# WL-FRONT.net
KiCad netlist of a schematic drawn in Altium Designer
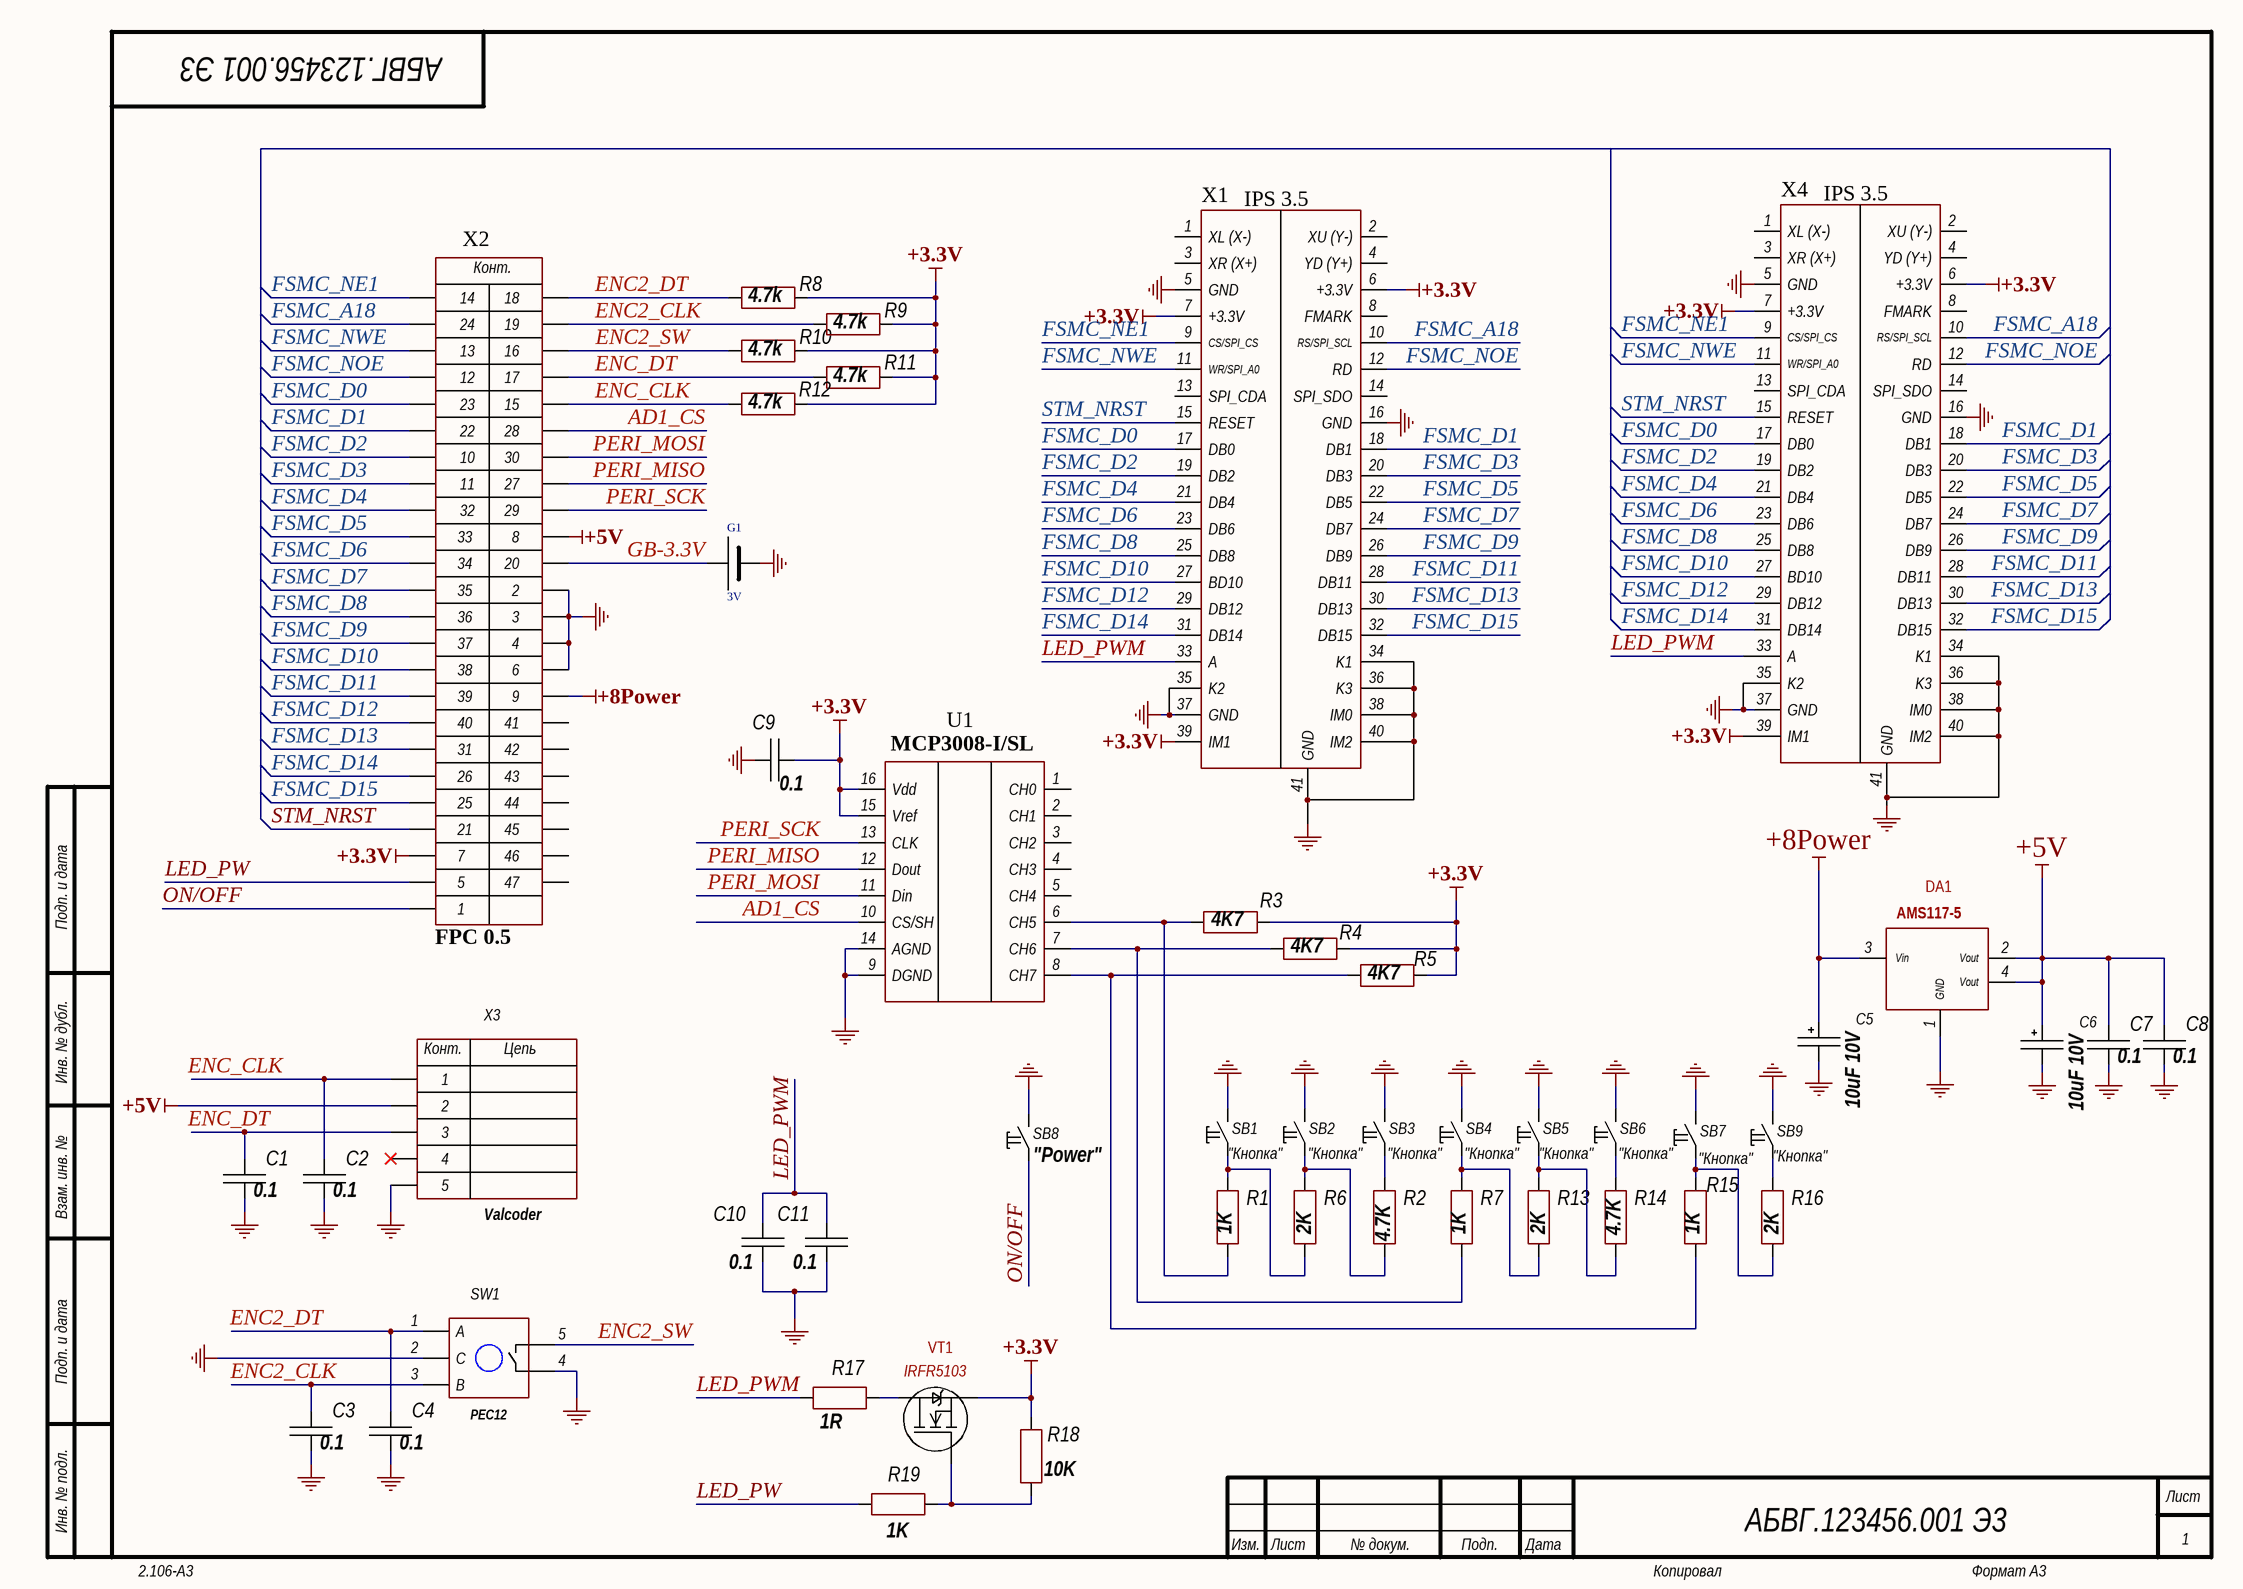
[diagram p0: WL-FRONT.SchDoc]

(export (version "E")
  (design (tool "Eeschema 10.0.6"))
  (components
    (comp (ref "C1")
      (value "0.1")
      (footprint "standard:CH0805C")
      (libsource (lib "Discrete") (part "Capacitor"))
    )
    (comp (ref "C2")
      (value "0.1")
      (footprint "standard:CH0805C")
      (libsource (lib "Discrete") (part "Capacitor"))
    )
    (comp (ref "C3")
      (value "0.1")
      (footprint "standard:CH0805C")
      (libsource (lib "Discrete") (part "Capacitor"))
    )
    (comp (ref "C4")
      (value "0.1")
      (footprint "standard:CH0805C")
      (libsource (lib "Discrete") (part "Capacitor"))
    )
    (comp (ref "C5")
      (value "10uF 10V")
      (footprint "standard:TANTAL_B")
      (libsource (lib "Discrete") (part "TantalCap"))
    )
    (comp (ref "C6")
      (value "10uF 10V")
      (footprint "standard:TANTAL_B")
      (libsource (lib "Discrete") (part "TantalCap"))
    )
    (comp (ref "C7")
      (value "0.1")
      (footprint "standard:CH0805C")
      (libsource (lib "Discrete") (part "Capacitor"))
    )
    (comp (ref "C8")
      (value "0.1")
      (footprint "standard:CH0805C")
      (libsource (lib "Discrete") (part "Capacitor"))
    )
    (comp (ref "C9")
      (value "0.1")
      (footprint "standard:CH0805C")
      (libsource (lib "Discrete") (part "Capacitor"))
    )
    (comp (ref "C10")
      (value "0.1")
      (footprint "standard:CH0805C")
      (libsource (lib "Discrete") (part "Capacitor"))
    )
    (comp (ref "C11")
      (value "0.1")
      (footprint "standard:CH0805C")
      (libsource (lib "Discrete") (part "Capacitor"))
    )
    (comp (ref "DA1") (value "AMS117-5") (footprint "SOT223") (libsource (lib "Analog") (part "AMS117")))
    (comp (ref "G1")
      (value "3V")
      (footprint "BAT: CH224-2032")
      (libsource (lib "Connectors") (part "POWER_BAT"))
    )
    (comp (ref "R1") (value "1K") (footprint "standard:CH0805R") (libsource (lib "") (part "Resistor_3")))
    (comp (ref "R2") (value "4.7K") (footprint "standard:CH0805R") (libsource (lib "") (part "Resistor_3")))
    (comp (ref "R3") (value "4K7") (footprint "standard:CH0805R") (libsource (lib "") (part "Resistor_2")))
    (comp (ref "R4") (value "4K7") (footprint "standard:CH0805R") (libsource (lib "") (part "Resistor_1")))
    (comp (ref "R5") (value "4K7") (footprint "standard:CH0805R") (libsource (lib "") (part "Resistor_2")))
    (comp (ref "R6") (value "2K") (footprint "standard:CH0805R") (libsource (lib "") (part "Resistor_3")))
    (comp (ref "R7") (value "1K") (footprint "standard:CH0805R") (libsource (lib "") (part "Resistor_3")))
    (comp (ref "R8")
      (value "4.7k")
      (footprint "standard:CH0805R")
      (libsource (lib "Discrete") (part "Resistor"))
    )
    (comp (ref "R9")
      (value "4.7k")
      (footprint "standard:CH0805R")
      (libsource (lib "Discrete") (part "Resistor"))
    )
    (comp (ref "R10")
      (value "4.7k")
      (footprint "standard:CH0805R")
      (libsource (lib "Discrete") (part "Resistor"))
    )
    (comp (ref "R11")
      (value "4.7k")
      (footprint "standard:CH0805R")
      (libsource (lib "Discrete") (part "Resistor"))
    )
    (comp (ref "R12")
      (value "4.7k")
      (footprint "standard:CH0805R")
      (libsource (lib "Discrete") (part "Resistor"))
    )
    (comp (ref "R13") (value "2K") (footprint "standard:CH0805R") (libsource (lib "") (part "Resistor_3")))
    (comp (ref "R14") (value "4.7K") (footprint "standard:CH0805R") (libsource (lib "") (part "Resistor_3")))
    (comp (ref "R15") (value "1K") (footprint "standard:CH0805R") (libsource (lib "") (part "Resistor_3")))
    (comp (ref "R16") (value "2K") (footprint "standard:CH0805R") (libsource (lib "") (part "Resistor_3")))
    (comp (ref "R17")
      (value "1R")
      (footprint "standard:CH0805R")
      (libsource (lib "Discrete") (part "Resistor"))
    )
    (comp (ref "R18") (value "10K") (footprint "standard:CH0805R") (libsource (lib "") (part "Resistor_3")))
    (comp (ref "R19")
      (value "1K")
      (footprint "standard:CH0805R")
      (libsource (lib "Discrete") (part "Resistor"))
    )
    (comp (ref "SB1")
      (value "\"Кнопка\"")
      (footprint "BUT: 5X5")
      (description "6x6 mm")
      (libsource (lib "Connectors") (part "Tactile switches"))
    )
    (comp (ref "SB2")
      (value "\"Кнопка\"")
      (footprint "BUT: 5X5")
      (description "6x6 mm")
      (libsource (lib "Connectors") (part "Tactile switches"))
    )
    (comp (ref "SB3")
      (value "\"Кнопка\"")
      (footprint "BUT: 5X5")
      (description "6x6 mm")
      (libsource (lib "Connectors") (part "Tactile switches"))
    )
    (comp (ref "SB4")
      (value "\"Кнопка\"")
      (footprint "BUT: 5X5")
      (description "6x6 mm")
      (libsource (lib "Connectors") (part "Tactile switches"))
    )
    (comp (ref "SB5")
      (value "\"Кнопка\"")
      (footprint "BUT: 5X5")
      (description "6x6 mm")
      (libsource (lib "Connectors") (part "Tactile switches"))
    )
    (comp (ref "SB6")
      (value "\"Кнопка\"")
      (footprint "BUT: 5X5")
      (description "6x6 mm")
      (libsource (lib "Connectors") (part "Tactile switches"))
    )
    (comp (ref "SB7")
      (value "\"Кнопка\"")
      (footprint "BUT: 5X5")
      (description "6x6 mm")
      (libsource (lib "Connectors") (part "Tactile switches"))
    )
    (comp (ref "SB8")
      (value "\"Power\"")
      (footprint "BUT: 5X5")
      (description "6x6 mm")
      (libsource (lib "Connectors") (part "Tactile switches"))
    )
    (comp (ref "SB9")
      (value "\"Кнопка\"")
      (footprint "BUT: 5X5")
      (description "6x6 mm")
      (libsource (lib "Connectors") (part "Tactile switches"))
    )
    (comp (ref "SW1")
      (value "PEC12")
      (footprint "Valkoder-m2")
      (description "Encoder")
      (libsource (lib "Connectors") (part "PEC12"))
    )
    (comp (ref "U1")
      (value "MCP3008-I/SL")
      (footprint "16-SOIC")
      (libsource (lib "Digital") (part "MCP3008-I/SL"))
    )
    (comp (ref "VT1")
      (value "IRFR5103")
      (footprint "SOT23_132")
      (libsource (lib "Transistor") (part "N-KANAL"))
    )
    (comp (ref "X1")
      (value "IPS 3.5")
      (footprint "FPC-40P 0.5mm")
      (libsource (lib "") (part "LCD-IPS 3.5_1"))
    )
    (comp (ref "X2")
      (value "FPC 0.5")
      (footprint "CON: PBD2x20")
      (libsource (lib "Connectors") (part "FPC-45-0.5"))
    )
    (comp (ref "X3")
      (value "Valcoder")
      (footprint "custom:CON: PLS-5")
      (libsource (lib "Connectors") (part "5-Connector"))
    )
    (comp (ref "X4")
      (value "IPS 3.5")
      (footprint "IPS 3.5 ILI9481")
      (libsource (lib "Digital") (part "LCD-IPS 3.5"))
    )
  )
  (nets
    (net (code "1") (name "+3.3V") (class "Default")
      (node (ref "C9") (pin "2") (pinfunction "2_2") (pintype "power_in"))
      (node (ref "R10") (pin "1") (pinfunction "1_1") (pintype "passive"))
      (node (ref "R11") (pin "1") (pinfunction "1_1") (pintype "passive"))
      (node (ref "R12") (pin "1") (pinfunction "1_1") (pintype "passive"))
      (node (ref "R18") (pin "2") (pinfunction "2_2") (pintype "passive"))
      (node (ref "R3") (pin "2") (pinfunction "2_2") (pintype "passive"))
      (node (ref "R4") (pin "2") (pinfunction "2_2") (pintype "passive"))
      (node (ref "R5") (pin "2") (pinfunction "2_2") (pintype "passive"))
      (node (ref "R8") (pin "1") (pinfunction "1_1") (pintype "passive"))
      (node (ref "R9") (pin "1") (pinfunction "1_1") (pintype "passive"))
      (node (ref "U1") (pin "15") (pinfunction "Vref_15") (pintype "passive"))
      (node (ref "U1") (pin "16") (pinfunction "Vdd_16") (pintype "passive"))
      (node (ref "VT1") (pin "2") (pinfunction "I_2") (pintype "passive"))
      (node (ref "X1") (pin "39") (pinfunction "IM1_39") (pintype "passive"))
      (node (ref "X1") (pin "6") (pinfunction "+3.3V_6") (pintype "passive"))
      (node (ref "X1") (pin "7") (pinfunction "+3.3V_7") (pintype "passive"))
      (node (ref "X2") (pin "7") (pinfunction "7_7") (pintype "power_in"))
      (node (ref "X4") (pin "39") (pinfunction "IM1_39") (pintype "passive"))
      (node (ref "X4") (pin "6") (pinfunction "+3.3V_6") (pintype "passive"))
      (node (ref "X4") (pin "7") (pinfunction "+3.3V_7") (pintype "passive"))
    )
    (net (code "2") (name "+5V") (class "Default")
      (node (ref "C6") (pin "1") (pinfunction "1_1") (pintype "power_in"))
      (node (ref "C7") (pin "1") (pinfunction "1_1") (pintype "power_in"))
      (node (ref "C8") (pin "1") (pinfunction "1_1") (pintype "power_in"))
      (node (ref "DA1") (pin "2") (pinfunction "Vout_2") (pintype "passive"))
      (node (ref "DA1") (pin "4") (pinfunction "Vout_4") (pintype "passive"))
      (node (ref "X2") (pin "8") (pinfunction "8_8") (pintype "power_in"))
      (node (ref "X3") (pin "2") (pinfunction "2_2") (pintype "passive"))
    )
    (net (code "3") (name "+8Power") (class "Default")
      (node (ref "C5") (pin "1") (pinfunction "1_1") (pintype "power_in"))
      (node (ref "DA1") (pin "3") (pinfunction "Vin_3") (pintype "passive"))
      (node (ref "X2") (pin "9") (pinfunction "9_9") (pintype "power_in"))
    )
    (net (code "4") (name "/AD1_CS") (class "Default")
      (node (ref "U1") (pin "10") (pinfunction "CS/SH_10") (pintype "passive"))
      (node (ref "X2") (pin "28") (pinfunction "28_28") (pintype "power_in"))
    )
    (net (code "5") (name "/ENC2_CLK") (class "Default")
      (node (ref "C3") (pin "1") (pinfunction "1_1") (pintype "power_in"))
      (node (ref "R9") (pin "2") (pinfunction "2_2") (pintype "passive"))
      (node (ref "SW1") (pin "3") (pinfunction "B_3") (pintype "passive"))
      (node (ref "X2") (pin "19") (pinfunction "19_19") (pintype "power_in"))
    )
    (net (code "6") (name "/ENC2_DT") (class "Default")
      (node (ref "C4") (pin "1") (pinfunction "1_1") (pintype "power_in"))
      (node (ref "R8") (pin "2") (pinfunction "2_2") (pintype "passive"))
      (node (ref "SW1") (pin "1") (pinfunction "A_1") (pintype "passive"))
      (node (ref "X2") (pin "18") (pinfunction "18_18") (pintype "power_in"))
    )
    (net (code "7") (name "/ENC2_SW") (class "Default")
      (node (ref "R10") (pin "2") (pinfunction "2_2") (pintype "passive"))
      (node (ref "SW1") (pin "5") (pinfunction "5_5") (pintype "passive"))
      (node (ref "X2") (pin "16") (pinfunction "16_16") (pintype "power_in"))
    )
    (net (code "8") (name "/ENC_CLK") (class "Default")
      (node (ref "C2") (pin "1") (pinfunction "1_1") (pintype "power_in"))
      (node (ref "R12") (pin "2") (pinfunction "2_2") (pintype "passive"))
      (node (ref "X2") (pin "15") (pinfunction "15_15") (pintype "power_in"))
      (node (ref "X3") (pin "1") (pinfunction "1_1") (pintype "passive"))
    )
    (net (code "9") (name "/ENC_DT") (class "Default")
      (node (ref "C1") (pin "1") (pinfunction "1_1") (pintype "power_in"))
      (node (ref "R11") (pin "2") (pinfunction "2_2") (pintype "passive"))
      (node (ref "X2") (pin "17") (pinfunction "17_17") (pintype "power_in"))
      (node (ref "X3") (pin "3") (pinfunction "3_3") (pintype "power_in"))
    )
    (net (code "10") (name "/FSMC_A18") (class "Default")
      (node (ref "X1") (pin "10") (pinfunction "RS/SPI_SCL_10") (pintype "passive"))
      (node (ref "X2") (pin "24") (pinfunction "24_24") (pintype "passive"))
      (node (ref "X4") (pin "10") (pinfunction "RS/SPI_SCL_10") (pintype "passive"))
    )
    (net (code "11") (name "/FSMC_D0") (class "Default")
      (node (ref "X1") (pin "17") (pinfunction "DB0_17") (pintype "passive"))
      (node (ref "X2") (pin "23") (pinfunction "23_23") (pintype "power_in"))
      (node (ref "X4") (pin "17") (pinfunction "DB0_17") (pintype "passive"))
    )
    (net (code "12") (name "/FSMC_D1") (class "Default")
      (node (ref "X1") (pin "18") (pinfunction "DB1_18") (pintype "passive"))
      (node (ref "X2") (pin "22") (pinfunction "22_22") (pintype "power_in"))
      (node (ref "X4") (pin "18") (pinfunction "DB1_18") (pintype "passive"))
    )
    (net (code "13") (name "/FSMC_D2") (class "Default")
      (node (ref "X1") (pin "19") (pinfunction "DB2_19") (pintype "passive"))
      (node (ref "X2") (pin "10") (pinfunction "10_10") (pintype "power_in"))
      (node (ref "X4") (pin "19") (pinfunction "DB2_19") (pintype "passive"))
    )
    (net (code "14") (name "/FSMC_D3") (class "Default")
      (node (ref "X1") (pin "20") (pinfunction "DB3_20") (pintype "passive"))
      (node (ref "X2") (pin "11") (pinfunction "11_11") (pintype "power_in"))
      (node (ref "X4") (pin "20") (pinfunction "DB3_20") (pintype "passive"))
    )
    (net (code "15") (name "/FSMC_D4") (class "Default")
      (node (ref "X1") (pin "21") (pinfunction "DB4_21") (pintype "passive"))
      (node (ref "X2") (pin "32") (pinfunction "32_32") (pintype "power_in"))
      (node (ref "X4") (pin "21") (pinfunction "DB4_21") (pintype "passive"))
    )
    (net (code "16") (name "/FSMC_D5") (class "Default")
      (node (ref "X1") (pin "22") (pinfunction "DB5_22") (pintype "passive"))
      (node (ref "X2") (pin "33") (pinfunction "33_33") (pintype "power_in"))
      (node (ref "X4") (pin "22") (pinfunction "DB5_22") (pintype "passive"))
    )
    (net (code "17") (name "/FSMC_D6") (class "Default")
      (node (ref "X1") (pin "23") (pinfunction "DB6_23") (pintype "passive"))
      (node (ref "X2") (pin "34") (pinfunction "34_34") (pintype "power_in"))
      (node (ref "X4") (pin "23") (pinfunction "DB6_23") (pintype "passive"))
    )
    (net (code "18") (name "/FSMC_D7") (class "Default")
      (node (ref "X1") (pin "24") (pinfunction "DB7_24") (pintype "passive"))
      (node (ref "X2") (pin "35") (pinfunction "35_35") (pintype "power_in"))
      (node (ref "X4") (pin "24") (pinfunction "DB7_24") (pintype "passive"))
    )
    (net (code "19") (name "/FSMC_D8") (class "Default")
      (node (ref "X1") (pin "25") (pinfunction "DB8_25") (pintype "passive"))
      (node (ref "X2") (pin "36") (pinfunction "36_36") (pintype "power_in"))
      (node (ref "X4") (pin "25") (pinfunction "DB8_25") (pintype "passive"))
    )
    (net (code "20") (name "/FSMC_D9") (class "Default")
      (node (ref "X1") (pin "26") (pinfunction "DB9_26") (pintype "passive"))
      (node (ref "X2") (pin "37") (pinfunction "37_37") (pintype "power_in"))
      (node (ref "X4") (pin "26") (pinfunction "DB9_26") (pintype "passive"))
    )
    (net (code "21") (name "/FSMC_D10") (class "Default")
      (node (ref "X1") (pin "27") (pinfunction "BD10_27") (pintype "passive"))
      (node (ref "X2") (pin "38") (pinfunction "38_38") (pintype "power_in"))
      (node (ref "X4") (pin "27") (pinfunction "BD10_27") (pintype "passive"))
    )
    (net (code "22") (name "/FSMC_D11") (class "Default")
      (node (ref "X1") (pin "28") (pinfunction "DB11_28") (pintype "passive"))
      (node (ref "X2") (pin "39") (pinfunction "39_39") (pintype "power_in"))
      (node (ref "X4") (pin "28") (pinfunction "DB11_28") (pintype "passive"))
    )
    (net (code "23") (name "/FSMC_D12") (class "Default")
      (node (ref "X1") (pin "29") (pinfunction "DB12_29") (pintype "passive"))
      (node (ref "X2") (pin "40") (pinfunction "40_40") (pintype "power_in"))
      (node (ref "X4") (pin "29") (pinfunction "DB12_29") (pintype "passive"))
    )
    (net (code "24") (name "/FSMC_D13") (class "Default")
      (node (ref "X1") (pin "30") (pinfunction "DB13_30") (pintype "passive"))
      (node (ref "X2") (pin "31") (pinfunction "31_31") (pintype "power_in"))
      (node (ref "X4") (pin "30") (pinfunction "DB13_30") (pintype "passive"))
    )
    (net (code "25") (name "/FSMC_D14") (class "Default")
      (node (ref "X1") (pin "31") (pinfunction "DB14_31") (pintype "passive"))
      (node (ref "X2") (pin "26") (pinfunction "26_26") (pintype "power_in"))
      (node (ref "X4") (pin "31") (pinfunction "DB14_31") (pintype "passive"))
    )
    (net (code "26") (name "/FSMC_D15") (class "Default")
      (node (ref "X1") (pin "32") (pinfunction "DB15_32") (pintype "passive"))
      (node (ref "X2") (pin "25") (pinfunction "25_25") (pintype "power_in"))
      (node (ref "X4") (pin "32") (pinfunction "DB15_32") (pintype "passive"))
    )
    (net (code "27") (name "/FSMC_NE1") (class "Default")
      (node (ref "X1") (pin "9") (pinfunction "CS/SPI_CS_9") (pintype "passive"))
      (node (ref "X2") (pin "14") (pinfunction "14_14") (pintype "passive"))
      (node (ref "X4") (pin "9") (pinfunction "CS/SPI_CS_9") (pintype "passive"))
    )
    (net (code "28") (name "/FSMC_NOE") (class "Default")
      (node (ref "X1") (pin "12") (pinfunction "RD_12") (pintype "passive"))
      (node (ref "X2") (pin "12") (pinfunction "12_12") (pintype "power_in"))
      (node (ref "X4") (pin "12") (pinfunction "RD_12") (pintype "passive"))
    )
    (net (code "29") (name "/FSMC_NWE") (class "Default")
      (node (ref "X1") (pin "11") (pinfunction "WR/SPI_A0_11") (pintype "passive"))
      (node (ref "X2") (pin "13") (pinfunction "13_13") (pintype "power_in"))
      (node (ref "X4") (pin "11") (pinfunction "WR/SPI_A0_11") (pintype "passive"))
    )
    (net (code "30") (name "/GB-3.3V") (class "Default")
      (node (ref "G1") (pin "1") (pinfunction "0_1") (pintype "passive"))
      (node (ref "X2") (pin "20") (pinfunction "20_20") (pintype "power_in"))
    )
    (net (code "31") (name "/LED_PW") (class "Default")
      (node (ref "R19") (pin "2") (pinfunction "2_2") (pintype "passive"))
      (node (ref "X2") (pin "5") (pinfunction "5_5") (pintype "power_in"))
    )
    (net (code "32") (name "/LED_PWM") (class "Default")
      (node (ref "C10") (pin "1") (pinfunction "1_1") (pintype "power_in"))
      (node (ref "C11") (pin "1") (pinfunction "1_1") (pintype "power_in"))
      (node (ref "R17") (pin "2") (pinfunction "2_2") (pintype "passive"))
      (node (ref "X1") (pin "33") (pinfunction "A_33") (pintype "passive"))
      (node (ref "X4") (pin "33") (pinfunction "A_33") (pintype "passive"))
    )
    (net (code "33") (name "/ON{slash}OFF") (class "Default")
      (node (ref "SB8") (pin "1") (pinfunction "1_1") (pintype "passive"))
      (node (ref "X2") (pin "1") (pinfunction "1_1") (pintype "power_in"))
    )
    (net (code "34") (name "/PERI_MISO") (class "Default")
      (node (ref "U1") (pin "12") (pinfunction "Dout_12") (pintype "passive"))
      (node (ref "X2") (pin "27") (pinfunction "27_27") (pintype "power_in"))
    )
    (net (code "35") (name "/PERI_MOSI") (class "Default")
      (node (ref "U1") (pin "11") (pinfunction "Din_11") (pintype "passive"))
      (node (ref "X2") (pin "30") (pinfunction "30_30") (pintype "power_in"))
    )
    (net (code "36") (name "/PERI_SCK") (class "Default")
      (node (ref "U1") (pin "13") (pinfunction "CLK_13") (pintype "passive"))
      (node (ref "X2") (pin "29") (pinfunction "29_29") (pintype "power_in"))
    )
    (net (code "37") (name "/STM_NRST") (class "Default")
      (node (ref "X1") (pin "15") (pinfunction "RESET_15") (pintype "passive"))
      (node (ref "X2") (pin "21") (pinfunction "21_21") (pintype "power_in"))
      (node (ref "X4") (pin "15") (pinfunction "RESET_15") (pintype "passive"))
    )
    (net (code "38") (name "GND") (class "Default")
      (node (ref "C1") (pin "2") (pinfunction "2_2") (pintype "power_in"))
      (node (ref "C10") (pin "2") (pinfunction "2_2") (pintype "power_in"))
      (node (ref "C11") (pin "2") (pinfunction "2_2") (pintype "power_in"))
      (node (ref "C2") (pin "2") (pinfunction "2_2") (pintype "power_in"))
      (node (ref "C3") (pin "2") (pinfunction "2_2") (pintype "power_in"))
      (node (ref "C4") (pin "2") (pinfunction "2_2") (pintype "power_in"))
      (node (ref "C5") (pin "2") (pinfunction "2_2") (pintype "power_in"))
      (node (ref "C6") (pin "2") (pinfunction "2_2") (pintype "power_in"))
      (node (ref "C7") (pin "2") (pinfunction "2_2") (pintype "power_in"))
      (node (ref "C8") (pin "2") (pinfunction "2_2") (pintype "power_in"))
      (node (ref "C9") (pin "1") (pinfunction "1_1") (pintype "power_in"))
      (node (ref "DA1") (pin "1") (pinfunction "GND_1") (pintype "passive"))
      (node (ref "G1") (pin "2") (pinfunction "1_2") (pintype "passive"))
      (node (ref "SB1") (pin "2") (pinfunction "2_2") (pintype "passive"))
      (node (ref "SB2") (pin "2") (pinfunction "2_2") (pintype "passive"))
      (node (ref "SB3") (pin "2") (pinfunction "2_2") (pintype "passive"))
      (node (ref "SB4") (pin "2") (pinfunction "2_2") (pintype "passive"))
      (node (ref "SB5") (pin "2") (pinfunction "2_2") (pintype "passive"))
      (node (ref "SB6") (pin "2") (pinfunction "2_2") (pintype "passive"))
      (node (ref "SB7") (pin "2") (pinfunction "2_2") (pintype "passive"))
      (node (ref "SB8") (pin "2") (pinfunction "2_2") (pintype "passive"))
      (node (ref "SB9") (pin "2") (pinfunction "2_2") (pintype "passive"))
      (node (ref "SW1") (pin "2") (pinfunction "C_2") (pintype "passive"))
      (node (ref "SW1") (pin "4") (pinfunction "4_4") (pintype "passive"))
      (node (ref "U1") (pin "14") (pinfunction "AGND_14") (pintype "passive"))
      (node (ref "U1") (pin "9") (pinfunction "DGND_9") (pintype "passive"))
      (node (ref "X1") (pin "16") (pinfunction "GND_16") (pintype "passive"))
      (node (ref "X1") (pin "34") (pinfunction "K1_34") (pintype "passive"))
      (node (ref "X1") (pin "35") (pinfunction "K2_35") (pintype "passive"))
      (node (ref "X1") (pin "36") (pinfunction "K3_36") (pintype "passive"))
      (node (ref "X1") (pin "37") (pinfunction "GND_37") (pintype "passive"))
      (node (ref "X1") (pin "38") (pinfunction "IM0_38") (pintype "passive"))
      (node (ref "X1") (pin "40") (pinfunction "IM2_40") (pintype "passive"))
      (node (ref "X1") (pin "41") (pinfunction "GND_41") (pintype "passive"))
      (node (ref "X1") (pin "5") (pinfunction "GND_5") (pintype "passive"))
      (node (ref "X2") (pin "2") (pinfunction "2_2") (pintype "power_in"))
      (node (ref "X2") (pin "3") (pinfunction "3_3") (pintype "power_in"))
      (node (ref "X2") (pin "4") (pinfunction "4_4") (pintype "power_in"))
      (node (ref "X2") (pin "6") (pinfunction "6_6") (pintype "power_in"))
      (node (ref "X3") (pin "5") (pinfunction "5_5") (pintype "power_in"))
      (node (ref "X4") (pin "16") (pinfunction "GND_16") (pintype "passive"))
      (node (ref "X4") (pin "34") (pinfunction "K1_34") (pintype "passive"))
      (node (ref "X4") (pin "35") (pinfunction "K2_35") (pintype "passive"))
      (node (ref "X4") (pin "36") (pinfunction "K3_36") (pintype "passive"))
      (node (ref "X4") (pin "37") (pinfunction "GND_37") (pintype "passive"))
      (node (ref "X4") (pin "38") (pinfunction "IM0_38") (pintype "passive"))
      (node (ref "X4") (pin "40") (pinfunction "IM2_40") (pintype "passive"))
      (node (ref "X4") (pin "41") (pinfunction "GND_41") (pintype "passive"))
      (node (ref "X4") (pin "5") (pinfunction "GND_5") (pintype "passive"))
    )
    (net (code "39") (name "Net-(R1-Pad2)") (class "Default")
      (node (ref "R1") (pin "2") (pinfunction "2_2") (pintype "passive"))
      (node (ref "R6") (pin "1") (pinfunction "1_1") (pintype "passive"))
      (node (ref "SB1") (pin "1") (pinfunction "1_1") (pintype "passive"))
    )
    (net (code "40") (name "Net-(R2-Pad1)") (class "Default")
      (node (ref "R2") (pin "1") (pinfunction "1_1") (pintype "passive"))
      (node (ref "R6") (pin "2") (pinfunction "2_2") (pintype "passive"))
      (node (ref "SB2") (pin "1") (pinfunction "1_1") (pintype "passive"))
    )
    (net (code "41") (name "Net-(R2-Pad2)") (class "Default")
      (node (ref "R2") (pin "2") (pinfunction "2_2") (pintype "passive"))
      (node (ref "SB3") (pin "1") (pinfunction "1_1") (pintype "passive"))
    )
    (net (code "42") (name "Net-(R13-Pad1)") (class "Default")
      (node (ref "R13") (pin "1") (pinfunction "1_1") (pintype "passive"))
      (node (ref "R7") (pin "2") (pinfunction "2_2") (pintype "passive"))
      (node (ref "SB4") (pin "1") (pinfunction "1_1") (pintype "passive"))
    )
    (net (code "43") (name "Net-(R13-Pad2)") (class "Default")
      (node (ref "R13") (pin "2") (pinfunction "2_2") (pintype "passive"))
      (node (ref "R14") (pin "1") (pinfunction "1_1") (pintype "passive"))
      (node (ref "SB5") (pin "1") (pinfunction "1_1") (pintype "passive"))
    )
    (net (code "44") (name "Net-(R14-Pad2)") (class "Default")
      (node (ref "R14") (pin "2") (pinfunction "2_2") (pintype "passive"))
      (node (ref "SB6") (pin "1") (pinfunction "1_1") (pintype "passive"))
    )
    (net (code "45") (name "Net-(R15-Pad2)") (class "Default")
      (node (ref "R15") (pin "2") (pinfunction "2_2") (pintype "passive"))
      (node (ref "R16") (pin "1") (pinfunction "1_1") (pintype "passive"))
      (node (ref "SB7") (pin "1") (pinfunction "1_1") (pintype "passive"))
    )
    (net (code "46") (name "Net-(R16-Pad2)") (class "Default")
      (node (ref "R16") (pin "2") (pinfunction "2_2") (pintype "passive"))
      (node (ref "SB9") (pin "1") (pinfunction "1_1") (pintype "passive"))
    )
    (net (code "47") (name "Net-(U1-CH5)") (class "Default")
      (node (ref "R1") (pin "1") (pinfunction "1_1") (pintype "passive"))
      (node (ref "R3") (pin "1") (pinfunction "1_1") (pintype "passive"))
      (node (ref "U1") (pin "6") (pinfunction "CH5_6") (pintype "passive"))
    )
    (net (code "48") (name "Net-(U1-CH6)") (class "Default")
      (node (ref "R4") (pin "1") (pinfunction "1_1") (pintype "passive"))
      (node (ref "R7") (pin "1") (pinfunction "1_1") (pintype "passive"))
      (node (ref "U1") (pin "7") (pinfunction "CH6_7") (pintype "passive"))
    )
    (net (code "49") (name "Net-(U1-CH7)") (class "Default")
      (node (ref "R15") (pin "1") (pinfunction "1_1") (pintype "passive"))
      (node (ref "R5") (pin "1") (pinfunction "1_1") (pintype "passive"))
      (node (ref "U1") (pin "8") (pinfunction "CH7_8") (pintype "passive"))
    )
    (net (code "50") (name "Net-(VT1-Затвор(Gate))") (class "Default")
      (node (ref "R18") (pin "1") (pinfunction "1_1") (pintype "passive"))
      (node (ref "R19") (pin "1") (pinfunction "1_1") (pintype "passive"))
      (node (ref "VT1") (pin "1") (pinfunction "Затвор(Gate)_1") (pintype "passive"))
    )
    (net (code "51") (name "Net-(VT1-Сток(Drain))") (class "Default")
      (node (ref "R17") (pin "1") (pinfunction "1_1") (pintype "passive"))
      (node (ref "VT1") (pin "3") (pinfunction "Сток(Drain)_3") (pintype "passive"))
    )
    (net (code "52") (name "unconnected-(U1-CH0-Pad1)") (class "Default")
      (node (ref "U1") (pin "1") (pinfunction "CH0_1") (pintype "passive"))
    )
    (net (code "53") (name "unconnected-(U1-CH1-Pad2)") (class "Default")
      (node (ref "U1") (pin "2") (pinfunction "CH1_2") (pintype "passive"))
    )
    (net (code "54") (name "unconnected-(U1-CH2-Pad3)") (class "Default")
      (node (ref "U1") (pin "3") (pinfunction "CH2_3") (pintype "passive"))
    )
    (net (code "55") (name "unconnected-(U1-CH3-Pad4)") (class "Default")
      (node (ref "U1") (pin "4") (pinfunction "CH3_4") (pintype "passive"))
    )
    (net (code "56") (name "unconnected-(U1-CH4-Pad5)") (class "Default")
      (node (ref "U1") (pin "5") (pinfunction "CH4_5") (pintype "passive"))
    )
    (net (code "57") (name "unconnected-(X1-FMARK-Pad8)") (class "Default")
      (node (ref "X1") (pin "8") (pinfunction "FMARK_8") (pintype "passive"))
    )
    (net (code "58") (name "unconnected-(X1-SPI_CDA-Pad13)") (class "Default")
      (node (ref "X1") (pin "13") (pinfunction "SPI_CDA_13") (pintype "passive"))
    )
    (net (code "59") (name "unconnected-(X1-SPI_SDO-Pad14)") (class "Default")
      (node (ref "X1") (pin "14") (pinfunction "SPI_SDO_14") (pintype "passive"))
    )
    (net (code "60") (name "unconnected-(X1-XL_(X-)-Pad1)") (class "Default")
      (node (ref "X1") (pin "1") (pinfunction "XL_(X-)_1") (pintype "passive"))
    )
    (net (code "61") (name "unconnected-(X1-XR_(X+)-Pad3)") (class "Default")
      (node (ref "X1") (pin "3") (pinfunction "XR_(X+)_3") (pintype "passive"))
    )
    (net (code "62") (name "unconnected-(X1-XU_(Y-)-Pad2)") (class "Default")
      (node (ref "X1") (pin "2") (pinfunction "XU_(Y-)_2") (pintype "passive"))
    )
    (net (code "63") (name "unconnected-(X1-YD_(Y+)-Pad4)") (class "Default")
      (node (ref "X1") (pin "4") (pinfunction "YD_(Y+)_4") (pintype "passive"))
    )
    (net (code "64") (name "unconnected-(X2-Pad41)") (class "Default")
      (node (ref "X2") (pin "41") (pinfunction "41_41") (pintype "power_in"))
    )
    (net (code "65") (name "unconnected-(X2-Pad42)") (class "Default")
      (node (ref "X2") (pin "42") (pinfunction "42_42") (pintype "power_in"))
    )
    (net (code "66") (name "unconnected-(X2-Pad43)") (class "Default")
      (node (ref "X2") (pin "43") (pinfunction "43_43") (pintype "power_in"))
    )
    (net (code "67") (name "unconnected-(X2-Pad44)") (class "Default")
      (node (ref "X2") (pin "44") (pinfunction "44_44") (pintype "power_in"))
    )
    (net (code "68") (name "unconnected-(X2-Pad45)") (class "Default")
      (node (ref "X2") (pin "45") (pinfunction "45_45") (pintype "power_in"))
    )
    (net (code "69") (name "unconnected-(X2-Pad46)") (class "Default")
      (node (ref "X2") (pin "46") (pinfunction "46_46") (pintype "power_in"))
    )
    (net (code "70") (name "unconnected-(X2-Pad47)") (class "Default")
      (node (ref "X2") (pin "47") (pinfunction "47_47") (pintype "power_in"))
    )
    (net (code "71") (name "unconnected-(X3-Pad4)") (class "Default")
      (node (ref "X3") (pin "4") (pinfunction "4_4") (pintype "power_in+no_connect"))
    )
    (net (code "72") (name "unconnected-(X4-FMARK-Pad8)") (class "Default")
      (node (ref "X4") (pin "8") (pinfunction "FMARK_8") (pintype "passive"))
    )
    (net (code "73") (name "unconnected-(X4-SPI_CDA-Pad13)") (class "Default")
      (node (ref "X4") (pin "13") (pinfunction "SPI_CDA_13") (pintype "passive"))
    )
    (net (code "74") (name "unconnected-(X4-SPI_SDO-Pad14)") (class "Default")
      (node (ref "X4") (pin "14") (pinfunction "SPI_SDO_14") (pintype "passive"))
    )
    (net (code "75") (name "unconnected-(X4-XL_(X-)-Pad1)") (class "Default")
      (node (ref "X4") (pin "1") (pinfunction "XL_(X-)_1") (pintype "passive"))
    )
    (net (code "76") (name "unconnected-(X4-XR_(X+)-Pad3)") (class "Default")
      (node (ref "X4") (pin "3") (pinfunction "XR_(X+)_3") (pintype "passive"))
    )
    (net (code "77") (name "unconnected-(X4-XU_(Y-)-Pad2)") (class "Default")
      (node (ref "X4") (pin "2") (pinfunction "XU_(Y-)_2") (pintype "passive"))
    )
    (net (code "78") (name "unconnected-(X4-YD_(Y+)-Pad4)") (class "Default")
      (node (ref "X4") (pin "4") (pinfunction "YD_(Y+)_4") (pintype "passive"))
    )
  )
)
